# MAPE-CUN-Large-032.net
KiCad netlist of a schematic drawn in EAGLE
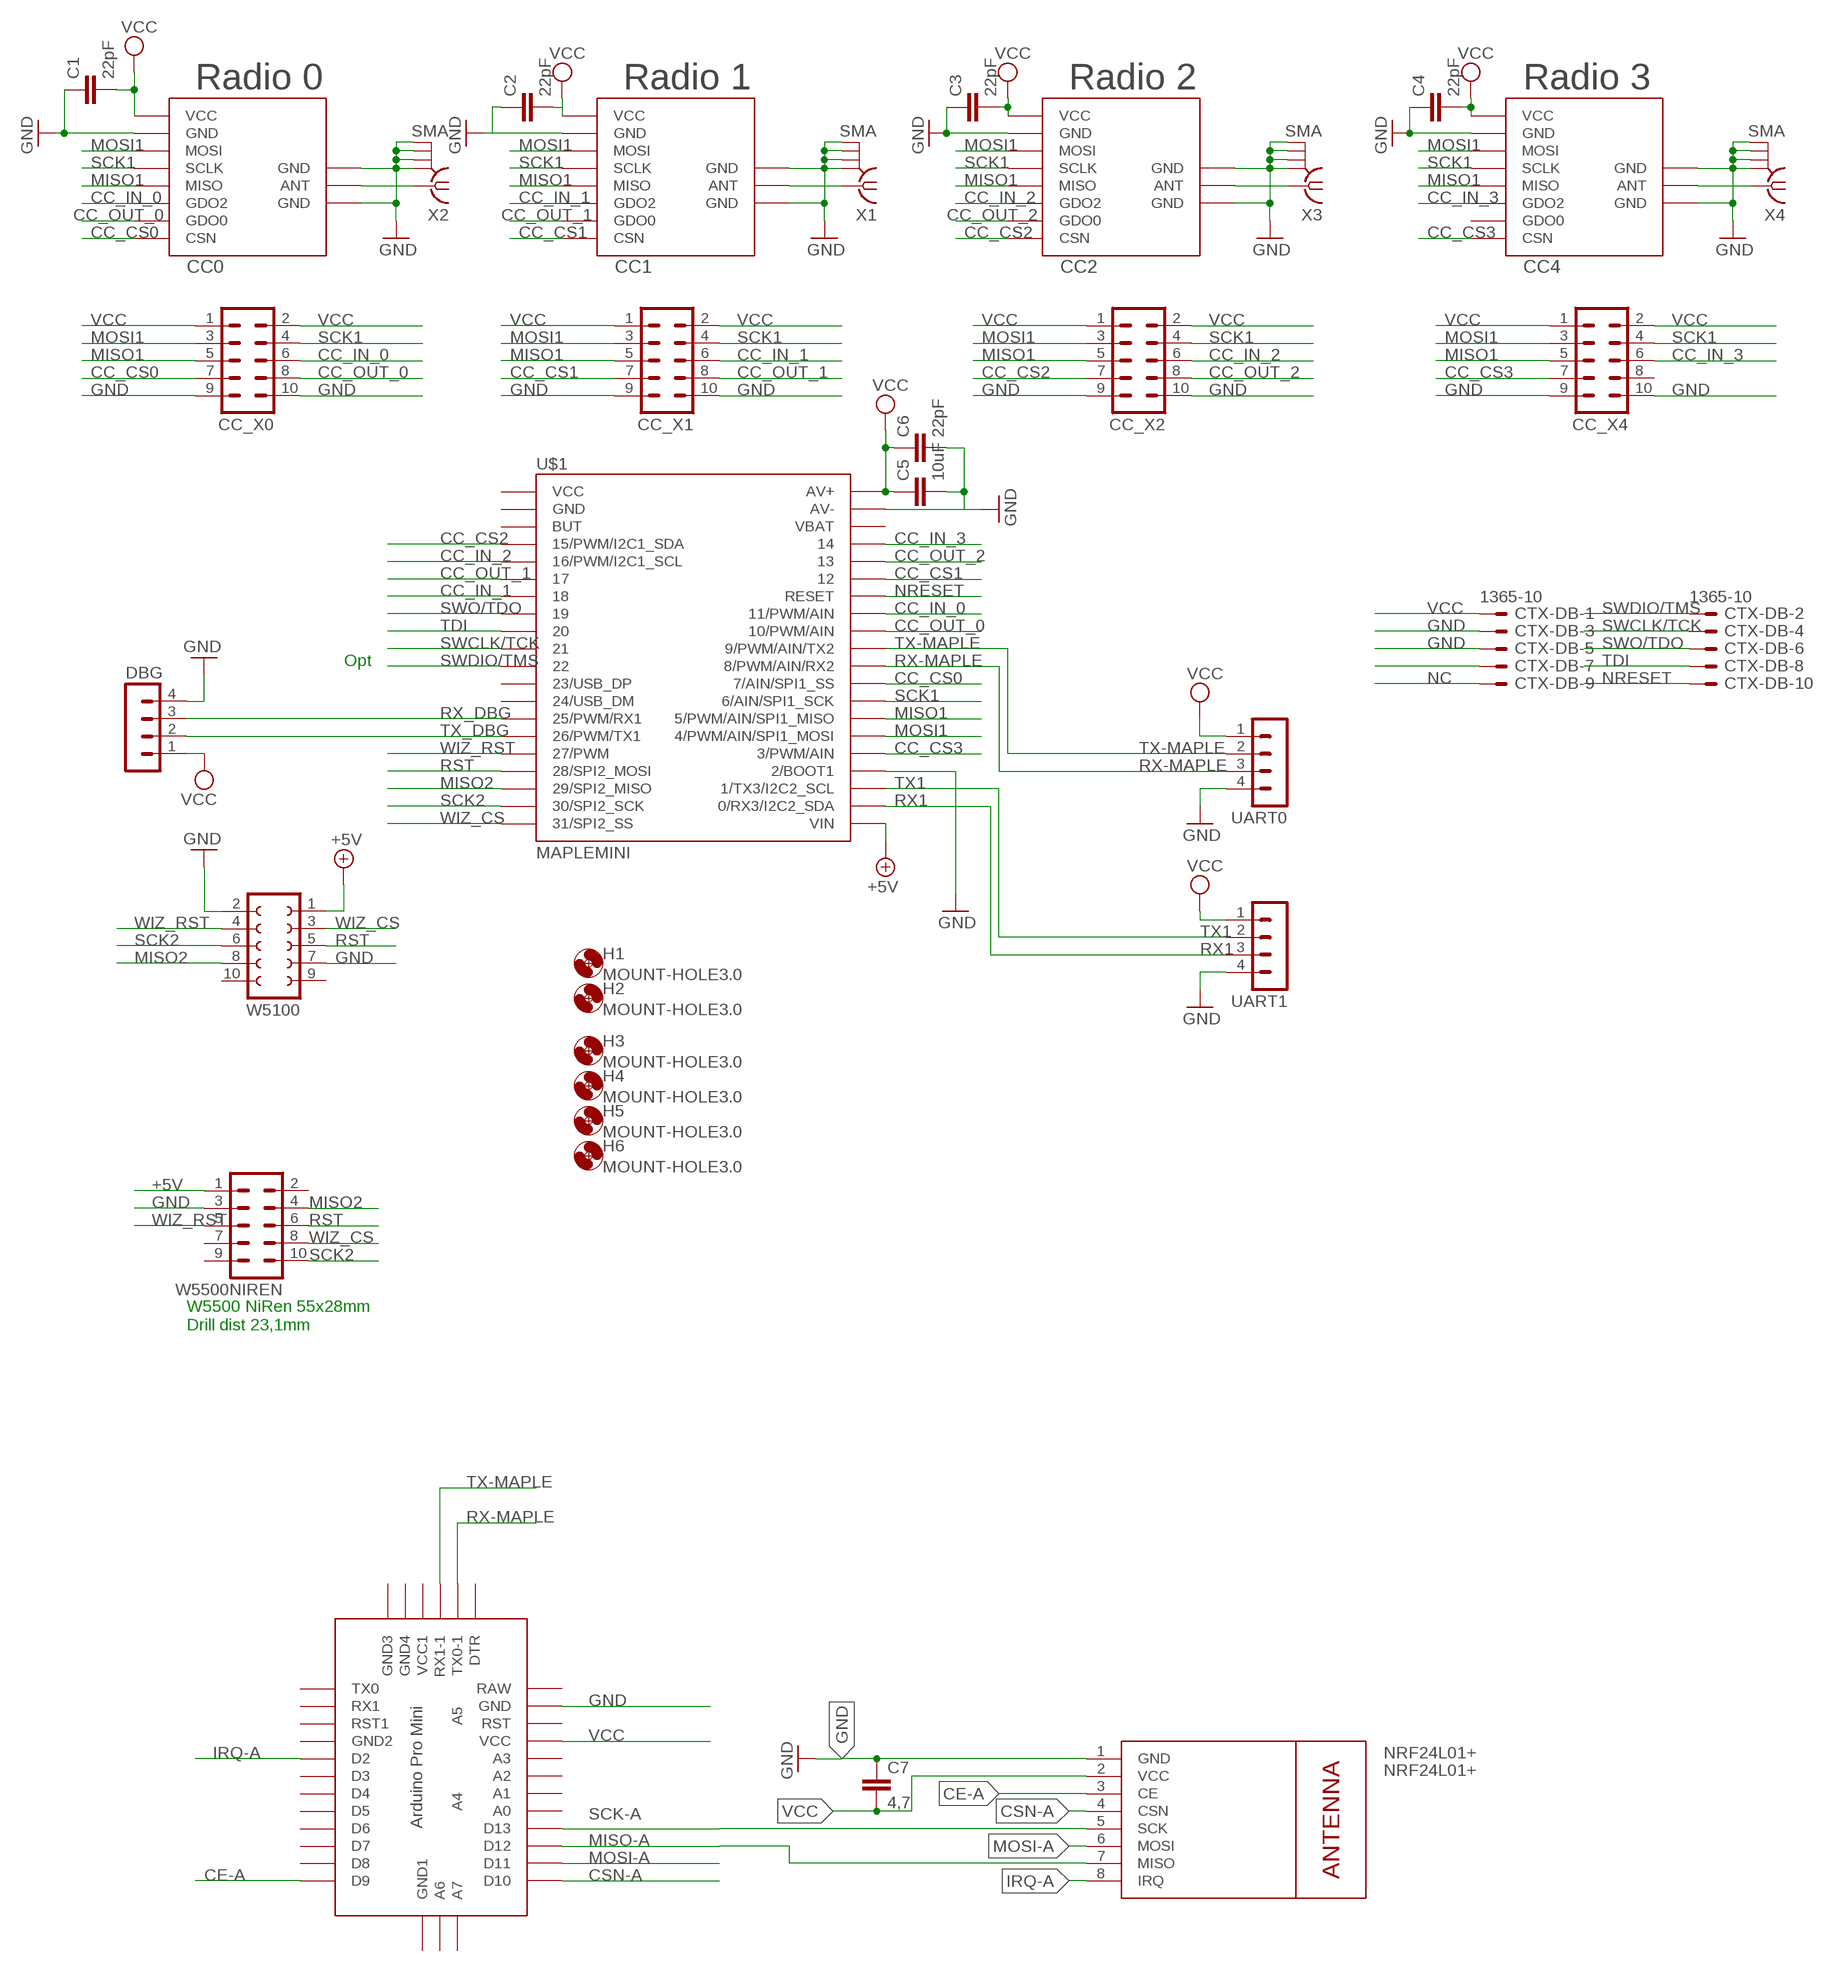
[diagram p0: schematic, sheet 1]

(export (version "E")
  (design (tool "Eeschema 10.0.6"))
  (components
    (comp (ref "C1")
      (value "22pF")
      (footprint "eagle-import:C0805")
      (libsource (lib "eagle-import") (part "C-EUC0805"))
    )
    (comp (ref "C2")
      (value "22pF")
      (footprint "eagle-import:C0805")
      (libsource (lib "eagle-import") (part "C-EUC0805"))
    )
    (comp (ref "C3")
      (value "22pF")
      (footprint "eagle-import:C0805")
      (libsource (lib "eagle-import") (part "C-EUC0805"))
    )
    (comp (ref "C4")
      (value "22pF")
      (footprint "eagle-import:C0805")
      (libsource (lib "eagle-import") (part "C-EUC0805"))
    )
    (comp (ref "C5")
      (value "10uF")
      (footprint "eagle-import:C1210")
      (libsource (lib "eagle-import") (part "C-EUC1210"))
    )
    (comp (ref "C6")
      (value "22pF")
      (footprint "eagle-import:C0805")
      (libsource (lib "eagle-import") (part "C-EUC0805"))
    )
    (comp (ref "C7")
      (value "4,7")
      (footprint "eagle-import:C1210")
      (libsource (lib "eagle-import") (part "C-EUC1210"))
    )
    (comp (ref "CC0")
      (value "CC1101_MODULE1SMD")
      (footprint "eagle-import:CC1101_MODULE1_SMD")
      (libsource (lib "eagle-import") (part "CC1101_MODULE1SMD"))
    )
    (comp (ref "CC1")
      (value "CC1101_MODULE1SMD")
      (footprint "eagle-import:CC1101_MODULE1_SMD")
      (libsource (lib "eagle-import") (part "CC1101_MODULE1SMD"))
    )
    (comp (ref "CC2")
      (value "CC1101_MODULE1SMD")
      (footprint "eagle-import:CC1101_MODULE1_SMD")
      (libsource (lib "eagle-import") (part "CC1101_MODULE1SMD"))
    )
    (comp (ref "CC4")
      (value "CC1101_MODULE1SMD")
      (footprint "eagle-import:CC1101_MODULE1_SMD")
      (libsource (lib "eagle-import") (part "CC1101_MODULE1SMD"))
    )
    (comp (ref "CC_X0")
      (value "MA05-2")
      (footprint "eagle-import:MA05-2")
      (libsource (lib "eagle-import") (part "MA05-2"))
    )
    (comp (ref "CC_X1")
      (value "MA05-2")
      (footprint "eagle-import:MA05-2")
      (libsource (lib "eagle-import") (part "MA05-2"))
    )
    (comp (ref "CC_X2")
      (value "MA05-2")
      (footprint "eagle-import:MA05-2")
      (libsource (lib "eagle-import") (part "MA05-2"))
    )
    (comp (ref "CC_X4")
      (value "MA05-2")
      (footprint "eagle-import:MA05-2")
      (libsource (lib "eagle-import") (part "MA05-2"))
    )
    (comp (ref "CTX-DB")
      (value "1365-10")
      (footprint "eagle-import:1365-10")
      (libsource (lib "eagle-import") (part "1365-10"))
    )
    (comp (ref "DBG")
      (value "MA04-1")
      (footprint "eagle-import:MA04-1")
      (libsource (lib "eagle-import") (part "MA04-1"))
    )
    (comp (ref "H1")
      (value "MOUNT-HOLE3.0")
      (footprint "eagle-import:3,0")
      (libsource (lib "eagle-import") (part "MOUNT-HOLE3.0"))
    )
    (comp (ref "H2")
      (value "MOUNT-HOLE3.0")
      (footprint "eagle-import:3,0")
      (libsource (lib "eagle-import") (part "MOUNT-HOLE3.0"))
    )
    (comp (ref "H3")
      (value "MOUNT-HOLE3.0")
      (footprint "eagle-import:3,0")
      (libsource (lib "eagle-import") (part "MOUNT-HOLE3.0"))
    )
    (comp (ref "H4")
      (value "MOUNT-HOLE3.0")
      (footprint "eagle-import:3,0")
      (libsource (lib "eagle-import") (part "MOUNT-HOLE3.0"))
    )
    (comp (ref "H5")
      (value "MOUNT-HOLE3.0")
      (footprint "eagle-import:3,0")
      (libsource (lib "eagle-import") (part "MOUNT-HOLE3.0"))
    )
    (comp (ref "H6")
      (value "MOUNT-HOLE3.0")
      (footprint "eagle-import:3,0")
      (libsource (lib "eagle-import") (part "MOUNT-HOLE3.0"))
    )
    (comp (ref "NRF24L01+")
      (value "NRF24L01+")
      (footprint "eagle-import:WIRELESS-NRF24L01")
      (libsource (lib "eagle-import") (part "WIRELESS-NRF24L01"))
    )
    (comp (ref "U$1")
      (value "MAPLEMINI")
      (footprint "eagle-import:20-DIP")
      (libsource (lib "eagle-import") (part "MAPLEMINI"))
    )
    (comp (ref "U$2")
      (value "ABK-PRO-MINI")
      (footprint "eagle-import:ABK-PRO-MINI")
      (libsource (lib "eagle-import") (part "ABK-PRO-MINI"))
    )
    (comp (ref "UART0")
      (value "MA04-1")
      (footprint "eagle-import:MA04-1")
      (libsource (lib "eagle-import") (part "MA04-1"))
    )
    (comp (ref "UART1")
      (value "MA04-1")
      (footprint "eagle-import:MA04-1")
      (libsource (lib "eagle-import") (part "MA04-1"))
    )
    (comp (ref "W5100")
      (value "FE05-2")
      (footprint "eagle-import:FE05-2")
      (libsource (lib "eagle-import") (part "FE05-2"))
    )
    (comp (ref "W5500NIREN")
      (value "MA05-2")
      (footprint "eagle-import:MA05-2")
      (libsource (lib "eagle-import") (part "MA05-2"))
    )
    (comp (ref "X1")
      (value "SMA")
      (footprint "eagle-import:SMA")
      (libsource (lib "eagle-import") (part "SMA"))
    )
    (comp (ref "X2")
      (value "SMA")
      (footprint "eagle-import:SMA")
      (libsource (lib "eagle-import") (part "SMA"))
    )
    (comp (ref "X3")
      (value "SMA")
      (footprint "eagle-import:SMA")
      (libsource (lib "eagle-import") (part "SMA"))
    )
    (comp (ref "X4")
      (value "SMA")
      (footprint "eagle-import:SMA")
      (libsource (lib "eagle-import") (part "SMA"))
    )
  )
  (nets
    (net (code "1") (name "+5V") (class "Default")
      (node (ref "U$1") (pin "21") (pinfunction "VIN_21") (pintype "bidirectional"))
      (node (ref "W5100") (pin "1") (pinfunction "1_1") (pintype "passive"))
      (node (ref "W5500NIREN") (pin "1") (pinfunction "1_1") (pintype "passive"))
    )
    (net (code "2") (name "/CC_CS0") (class "Default")
      (node (ref "CC0") (pin "CSN") (pinfunction "CSN_CSN") (pintype "bidirectional"))
      (node (ref "CC_X0") (pin "7") (pinfunction "7_7") (pintype "passive"))
      (node (ref "U$1") (pin "29") (pinfunction "7/AIN/SPI1_SS_29") (pintype "bidirectional"))
    )
    (net (code "3") (name "/CC_CS1") (class "Default")
      (node (ref "CC1") (pin "CSN") (pinfunction "CSN_CSN") (pintype "bidirectional"))
      (node (ref "CC_X1") (pin "7") (pinfunction "7_7") (pintype "passive"))
      (node (ref "U$1") (pin "35") (pinfunction "12_35") (pintype "bidirectional"))
    )
    (net (code "4") (name "/CC_CS2") (class "Default")
      (node (ref "CC2") (pin "CSN") (pinfunction "CSN_CSN") (pintype "bidirectional"))
      (node (ref "CC_X2") (pin "7") (pinfunction "7_7") (pintype "passive"))
      (node (ref "U$1") (pin "4") (pinfunction "15/PWM/I2C1_SDA_4") (pintype "bidirectional"))
    )
    (net (code "5") (name "/CC_CS3") (class "Default")
      (node (ref "CC4") (pin "CSN") (pinfunction "CSN_CSN") (pintype "bidirectional"))
      (node (ref "CC_X4") (pin "7") (pinfunction "7_7") (pintype "passive"))
      (node (ref "U$1") (pin "25") (pinfunction "3/PWM/AIN_25") (pintype "bidirectional"))
    )
    (net (code "6") (name "/CC_IN_0") (class "Default")
      (node (ref "CC0") (pin "GDO2") (pinfunction "GDO2_GDO2") (pintype "bidirectional"))
      (node (ref "CC_X0") (pin "6") (pinfunction "6_6") (pintype "passive"))
      (node (ref "U$1") (pin "33") (pinfunction "11/PWM/AIN_33") (pintype "bidirectional"))
    )
    (net (code "7") (name "/CC_IN_1") (class "Default")
      (node (ref "CC1") (pin "GDO2") (pinfunction "GDO2_GDO2") (pintype "bidirectional"))
      (node (ref "CC_X1") (pin "6") (pinfunction "6_6") (pintype "passive"))
      (node (ref "U$1") (pin "7") (pinfunction "18_7") (pintype "bidirectional"))
    )
    (net (code "8") (name "/CC_IN_2") (class "Default")
      (node (ref "CC2") (pin "GDO2") (pinfunction "GDO2_GDO2") (pintype "bidirectional"))
      (node (ref "CC_X2") (pin "6") (pinfunction "6_6") (pintype "passive"))
      (node (ref "U$1") (pin "5") (pinfunction "16/PWM/I2C1_SCL_5") (pintype "bidirectional"))
    )
    (net (code "9") (name "/CC_IN_3") (class "Default")
      (node (ref "CC4") (pin "GDO2") (pinfunction "GDO2_GDO2") (pintype "bidirectional"))
      (node (ref "CC_X4") (pin "6") (pinfunction "6_6") (pintype "passive"))
      (node (ref "U$1") (pin "37") (pinfunction "14_37") (pintype "bidirectional"))
    )
    (net (code "10") (name "/CC_OUT_0") (class "Default")
      (node (ref "CC0") (pin "GDO0") (pinfunction "GDO0_GDO0") (pintype "bidirectional"))
      (node (ref "CC_X0") (pin "8") (pinfunction "8_8") (pintype "passive"))
      (node (ref "U$1") (pin "32") (pinfunction "10/PWM/AIN_32") (pintype "bidirectional"))
    )
    (net (code "11") (name "/CC_OUT_1") (class "Default")
      (node (ref "CC1") (pin "GDO0") (pinfunction "GDO0_GDO0") (pintype "bidirectional"))
      (node (ref "CC_X1") (pin "8") (pinfunction "8_8") (pintype "passive"))
      (node (ref "U$1") (pin "6") (pinfunction "17_6") (pintype "bidirectional"))
    )
    (net (code "12") (name "/CC_OUT_2") (class "Default")
      (node (ref "CC2") (pin "GDO0") (pinfunction "GDO0_GDO0") (pintype "bidirectional"))
      (node (ref "CC_X2") (pin "8") (pinfunction "8_8") (pintype "passive"))
      (node (ref "U$1") (pin "36") (pinfunction "13_36") (pintype "bidirectional"))
    )
    (net (code "13") (name "/MISO-A") (class "Default")
      (node (ref "NRF24L01+") (pin "7") (pinfunction "MISO_7") (pintype "bidirectional"))
      (node (ref "U$2") (pin "D12") (pinfunction "D12_D12") (pintype "bidirectional"))
    )
    (net (code "14") (name "/MISO1") (class "Default")
      (node (ref "CC0") (pin "MISO") (pinfunction "MISO_MISO") (pintype "bidirectional"))
      (node (ref "CC1") (pin "MISO") (pinfunction "MISO_MISO") (pintype "bidirectional"))
      (node (ref "CC2") (pin "MISO") (pinfunction "MISO_MISO") (pintype "bidirectional"))
      (node (ref "CC4") (pin "MISO") (pinfunction "MISO_MISO") (pintype "bidirectional"))
      (node (ref "CC_X0") (pin "5") (pinfunction "5_5") (pintype "passive"))
      (node (ref "CC_X1") (pin "5") (pinfunction "5_5") (pintype "passive"))
      (node (ref "CC_X2") (pin "5") (pinfunction "5_5") (pintype "passive"))
      (node (ref "CC_X4") (pin "5") (pinfunction "5_5") (pintype "passive"))
      (node (ref "U$1") (pin "27") (pinfunction "5/PWM/AIN/SPI1_MISO_27") (pintype "bidirectional"))
    )
    (net (code "15") (name "/MISO2") (class "Default")
      (node (ref "U$1") (pin "18") (pinfunction "29/SPI2_MISO_18") (pintype "bidirectional"))
      (node (ref "W5100") (pin "8") (pinfunction "8_8") (pintype "passive"))
      (node (ref "W5500NIREN") (pin "4") (pinfunction "4_4") (pintype "passive"))
    )
    (net (code "16") (name "/MOSI1") (class "Default")
      (node (ref "CC0") (pin "MOSI") (pinfunction "MOSI_MOSI") (pintype "bidirectional"))
      (node (ref "CC1") (pin "MOSI") (pinfunction "MOSI_MOSI") (pintype "bidirectional"))
      (node (ref "CC2") (pin "MOSI") (pinfunction "MOSI_MOSI") (pintype "bidirectional"))
      (node (ref "CC4") (pin "MOSI") (pinfunction "MOSI_MOSI") (pintype "bidirectional"))
      (node (ref "CC_X0") (pin "3") (pinfunction "3_3") (pintype "passive"))
      (node (ref "CC_X1") (pin "3") (pinfunction "3_3") (pintype "passive"))
      (node (ref "CC_X2") (pin "3") (pinfunction "3_3") (pintype "passive"))
      (node (ref "CC_X4") (pin "3") (pinfunction "3_3") (pintype "passive"))
      (node (ref "U$1") (pin "26") (pinfunction "4/PWM/AIN/SPI1_MOSI_26") (pintype "bidirectional"))
    )
    (net (code "17") (name "/NC") (class "Default")
      (node (ref "CTX-DB") (pin "9") (pinfunction "S_9") (pintype "passive"))
    )
    (net (code "18") (name "/NRESET") (class "Default")
      (node (ref "CTX-DB") (pin "10") (pinfunction "S_10") (pintype "passive"))
      (node (ref "U$1") (pin "34") (pinfunction "RESET_34") (pintype "bidirectional"))
    )
    (net (code "19") (name "/RST") (class "Default")
      (node (ref "U$1") (pin "17") (pinfunction "28/SPI2_MOSI_17") (pintype "bidirectional"))
      (node (ref "W5100") (pin "5") (pinfunction "5_5") (pintype "passive"))
      (node (ref "W5500NIREN") (pin "6") (pinfunction "6_6") (pintype "passive"))
    )
    (net (code "20") (name "/RX-MAPLE") (class "Default")
      (node (ref "U$1") (pin "30") (pinfunction "8/PWM/AIN/RX2_30") (pintype "bidirectional"))
      (node (ref "U$2") (pin "TX0-1") (pinfunction "TX0-1_TX0-1") (pintype "bidirectional"))
      (node (ref "UART0") (pin "3") (pinfunction "3_3") (pintype "passive"))
    )
    (net (code "21") (name "/RX1") (class "Default")
      (node (ref "U$1") (pin "22") (pinfunction "0/RX3/I2C2_SDA_22") (pintype "bidirectional"))
      (node (ref "UART1") (pin "3") (pinfunction "3_3") (pintype "passive"))
    )
    (net (code "22") (name "/RX_DBG") (class "Default")
      (node (ref "DBG") (pin "3") (pinfunction "3_3") (pintype "passive"))
      (node (ref "U$1") (pin "14") (pinfunction "25/PWM/RX1_14") (pintype "bidirectional"))
    )
    (net (code "23") (name "/SCK-A") (class "Default")
      (node (ref "NRF24L01+") (pin "5") (pinfunction "SCK_5") (pintype "bidirectional"))
      (node (ref "U$2") (pin "D13") (pinfunction "D13_D13") (pintype "bidirectional"))
    )
    (net (code "24") (name "/SCK1") (class "Default")
      (node (ref "CC0") (pin "SCLK") (pinfunction "SCLK_SCLK") (pintype "bidirectional"))
      (node (ref "CC1") (pin "SCLK") (pinfunction "SCLK_SCLK") (pintype "bidirectional"))
      (node (ref "CC2") (pin "SCLK") (pinfunction "SCLK_SCLK") (pintype "bidirectional"))
      (node (ref "CC4") (pin "SCLK") (pinfunction "SCLK_SCLK") (pintype "bidirectional"))
      (node (ref "CC_X0") (pin "4") (pinfunction "4_4") (pintype "passive"))
      (node (ref "CC_X1") (pin "4") (pinfunction "4_4") (pintype "passive"))
      (node (ref "CC_X2") (pin "4") (pinfunction "4_4") (pintype "passive"))
      (node (ref "CC_X4") (pin "4") (pinfunction "4_4") (pintype "passive"))
      (node (ref "U$1") (pin "28") (pinfunction "6/AIN/SPI1_SCK_28") (pintype "bidirectional"))
    )
    (net (code "25") (name "/SCK2") (class "Default")
      (node (ref "U$1") (pin "19") (pinfunction "30/SPI2_SCK_19") (pintype "bidirectional"))
      (node (ref "W5100") (pin "6") (pinfunction "6_6") (pintype "passive"))
      (node (ref "W5500NIREN") (pin "10") (pinfunction "10_10") (pintype "passive"))
    )
    (net (code "26") (name "/SWCLK{slash}TCK") (class "Default")
      (node (ref "CTX-DB") (pin "4") (pinfunction "S_4") (pintype "passive"))
      (node (ref "U$1") (pin "10") (pinfunction "21_10") (pintype "bidirectional"))
    )
    (net (code "27") (name "/SWDIO{slash}TMS") (class "Default")
      (node (ref "CTX-DB") (pin "2") (pinfunction "S_2") (pintype "passive"))
      (node (ref "U$1") (pin "11") (pinfunction "22_11") (pintype "bidirectional"))
    )
    (net (code "28") (name "/SWO{slash}TDO") (class "Default")
      (node (ref "CTX-DB") (pin "6") (pinfunction "S_6") (pintype "passive"))
      (node (ref "U$1") (pin "8") (pinfunction "19_8") (pintype "bidirectional"))
    )
    (net (code "29") (name "/TDI") (class "Default")
      (node (ref "CTX-DB") (pin "8") (pinfunction "S_8") (pintype "passive"))
      (node (ref "U$1") (pin "9") (pinfunction "20_9") (pintype "bidirectional"))
    )
    (net (code "30") (name "/TX-MAPLE") (class "Default")
      (node (ref "U$1") (pin "31") (pinfunction "9/PWM/AIN/TX2_31") (pintype "bidirectional"))
      (node (ref "U$2") (pin "RX1-1") (pinfunction "RX1-1_RX1-1") (pintype "bidirectional"))
      (node (ref "UART0") (pin "2") (pinfunction "2_2") (pintype "passive"))
    )
    (net (code "31") (name "/TX1") (class "Default")
      (node (ref "U$1") (pin "23") (pinfunction "1/TX3/I2C2_SCL_23") (pintype "bidirectional"))
      (node (ref "UART1") (pin "2") (pinfunction "2_2") (pintype "passive"))
    )
    (net (code "32") (name "/TX_DBG") (class "Default")
      (node (ref "DBG") (pin "2") (pinfunction "2_2") (pintype "passive"))
      (node (ref "U$1") (pin "15") (pinfunction "26/PWM/TX1_15") (pintype "bidirectional"))
    )
    (net (code "33") (name "/WIZ_CS") (class "Default")
      (node (ref "U$1") (pin "20") (pinfunction "31/SPI2_SS_20") (pintype "bidirectional"))
      (node (ref "W5100") (pin "3") (pinfunction "3_3") (pintype "passive"))
      (node (ref "W5500NIREN") (pin "8") (pinfunction "8_8") (pintype "passive"))
    )
    (net (code "34") (name "/WIZ_RST") (class "Default")
      (node (ref "U$1") (pin "16") (pinfunction "27/PWM_16") (pintype "bidirectional"))
      (node (ref "W5100") (pin "4") (pinfunction "4_4") (pintype "passive"))
      (node (ref "W5500NIREN") (pin "5") (pinfunction "5_5") (pintype "passive"))
    )
    (net (code "35") (name "CE-A") (class "Default")
      (node (ref "NRF24L01+") (pin "3") (pinfunction "CE_3") (pintype "bidirectional"))
      (node (ref "U$2") (pin "D9") (pinfunction "D9_D9") (pintype "bidirectional"))
    )
    (net (code "36") (name "CSN-A") (class "Default")
      (node (ref "NRF24L01+") (pin "4") (pinfunction "CSN_4") (pintype "bidirectional"))
      (node (ref "U$2") (pin "D10") (pinfunction "D10_D10") (pintype "bidirectional"))
    )
    (net (code "37") (name "GND") (class "Default")
      (node (ref "C1") (pin "1") (pinfunction "1_1") (pintype "passive"))
      (node (ref "C2") (pin "1") (pinfunction "1_1") (pintype "passive"))
      (node (ref "C3") (pin "1") (pinfunction "1_1") (pintype "passive"))
      (node (ref "C4") (pin "1") (pinfunction "1_1") (pintype "passive"))
      (node (ref "C5") (pin "2") (pinfunction "2_2") (pintype "passive"))
      (node (ref "C6") (pin "2") (pinfunction "2_2") (pintype "passive"))
      (node (ref "C7") (pin "1") (pinfunction "1_1") (pintype "passive"))
      (node (ref "CC0") (pin "GND@0") (pinfunction "GND_GND@0") (pintype "power_in"))
      (node (ref "CC0") (pin "GND@1") (pinfunction "GND_GND@1") (pintype "power_in"))
      (node (ref "CC0") (pin "GND@2") (pinfunction "GND_GND@2") (pintype "power_in"))
      (node (ref "CC1") (pin "GND@0") (pinfunction "GND_GND@0") (pintype "power_in"))
      (node (ref "CC1") (pin "GND@1") (pinfunction "GND_GND@1") (pintype "power_in"))
      (node (ref "CC1") (pin "GND@2") (pinfunction "GND_GND@2") (pintype "power_in"))
      (node (ref "CC2") (pin "GND@0") (pinfunction "GND_GND@0") (pintype "power_in"))
      (node (ref "CC2") (pin "GND@1") (pinfunction "GND_GND@1") (pintype "power_in"))
      (node (ref "CC2") (pin "GND@2") (pinfunction "GND_GND@2") (pintype "power_in"))
      (node (ref "CC4") (pin "GND@0") (pinfunction "GND_GND@0") (pintype "power_in"))
      (node (ref "CC4") (pin "GND@1") (pinfunction "GND_GND@1") (pintype "power_in"))
      (node (ref "CC4") (pin "GND@2") (pinfunction "GND_GND@2") (pintype "power_in"))
      (node (ref "CC_X0") (pin "10") (pinfunction "10_10") (pintype "passive"))
      (node (ref "CC_X0") (pin "9") (pinfunction "9_9") (pintype "passive"))
      (node (ref "CC_X1") (pin "10") (pinfunction "10_10") (pintype "passive"))
      (node (ref "CC_X1") (pin "9") (pinfunction "9_9") (pintype "passive"))
      (node (ref "CC_X2") (pin "10") (pinfunction "10_10") (pintype "passive"))
      (node (ref "CC_X2") (pin "9") (pinfunction "9_9") (pintype "passive"))
      (node (ref "CC_X4") (pin "10") (pinfunction "10_10") (pintype "passive"))
      (node (ref "CC_X4") (pin "9") (pinfunction "9_9") (pintype "passive"))
      (node (ref "CTX-DB") (pin "3") (pinfunction "S_3") (pintype "passive"))
      (node (ref "CTX-DB") (pin "5") (pinfunction "S_5") (pintype "passive"))
      (node (ref "DBG") (pin "4") (pinfunction "4_4") (pintype "passive"))
      (node (ref "NRF24L01+") (pin "1") (pinfunction "GND_1") (pintype "power_in"))
      (node (ref "U$1") (pin "24") (pinfunction "2/BOOT1_24") (pintype "bidirectional"))
      (node (ref "U$1") (pin "39") (pinfunction "AV-_39") (pintype "bidirectional"))
      (node (ref "U$2") (pin "GND") (pinfunction "GND_GND") (pintype "bidirectional"))
      (node (ref "UART0") (pin "4") (pinfunction "4_4") (pintype "passive"))
      (node (ref "UART1") (pin "4") (pinfunction "4_4") (pintype "passive"))
      (node (ref "W5100") (pin "2") (pinfunction "2_2") (pintype "passive"))
      (node (ref "W5100") (pin "7") (pinfunction "7_7") (pintype "passive"))
      (node (ref "W5500NIREN") (pin "3") (pinfunction "3_3") (pintype "passive"))
      (node (ref "X1") (pin "GND@1") (pinfunction "2_GND@1") (pintype "passive"))
      (node (ref "X1") (pin "GND@2") (pinfunction "3_GND@2") (pintype "passive"))
      (node (ref "X1") (pin "GND@3") (pinfunction "4_GND@3") (pintype "passive"))
      (node (ref "X1") (pin "GND@4") (pinfunction "5_GND@4") (pintype "passive"))
      (node (ref "X2") (pin "GND@1") (pinfunction "2_GND@1") (pintype "passive"))
      (node (ref "X2") (pin "GND@2") (pinfunction "3_GND@2") (pintype "passive"))
      (node (ref "X2") (pin "GND@3") (pinfunction "4_GND@3") (pintype "passive"))
      (node (ref "X2") (pin "GND@4") (pinfunction "5_GND@4") (pintype "passive"))
      (node (ref "X3") (pin "GND@1") (pinfunction "2_GND@1") (pintype "passive"))
      (node (ref "X3") (pin "GND@2") (pinfunction "3_GND@2") (pintype "passive"))
      (node (ref "X3") (pin "GND@3") (pinfunction "4_GND@3") (pintype "passive"))
      (node (ref "X3") (pin "GND@4") (pinfunction "5_GND@4") (pintype "passive"))
      (node (ref "X4") (pin "GND@1") (pinfunction "2_GND@1") (pintype "passive"))
      (node (ref "X4") (pin "GND@2") (pinfunction "3_GND@2") (pintype "passive"))
      (node (ref "X4") (pin "GND@3") (pinfunction "4_GND@3") (pintype "passive"))
      (node (ref "X4") (pin "GND@4") (pinfunction "5_GND@4") (pintype "passive"))
    )
    (net (code "38") (name "IRQ-A") (class "Default")
      (node (ref "NRF24L01+") (pin "8") (pinfunction "IRQ_8") (pintype "bidirectional"))
      (node (ref "U$2") (pin "D2") (pinfunction "D2_D2") (pintype "bidirectional"))
    )
    (net (code "39") (name "MOSI-A") (class "Default")
      (node (ref "NRF24L01+") (pin "6") (pinfunction "MOSI_6") (pintype "bidirectional"))
      (node (ref "U$2") (pin "D11") (pinfunction "D11_D11") (pintype "bidirectional"))
    )
    (net (code "40") (name "Net-(CC0-PadANT)") (class "Default")
      (node (ref "CC0") (pin "ANT") (pinfunction "ANT_ANT") (pintype "output"))
      (node (ref "X2") (pin "1") (pinfunction "1_1") (pintype "passive"))
    )
    (net (code "41") (name "Net-(CC1-PadANT)") (class "Default")
      (node (ref "CC1") (pin "ANT") (pinfunction "ANT_ANT") (pintype "output"))
      (node (ref "X1") (pin "1") (pinfunction "1_1") (pintype "passive"))
    )
    (net (code "42") (name "Net-(CC2-PadANT)") (class "Default")
      (node (ref "CC2") (pin "ANT") (pinfunction "ANT_ANT") (pintype "output"))
      (node (ref "X3") (pin "1") (pinfunction "1_1") (pintype "passive"))
    )
    (net (code "43") (name "Net-(CC4-PadANT)") (class "Default")
      (node (ref "CC4") (pin "ANT") (pinfunction "ANT_ANT") (pintype "output"))
      (node (ref "X4") (pin "1") (pinfunction "1_1") (pintype "passive"))
    )
    (net (code "44") (name "VCC") (class "Default")
      (node (ref "C1") (pin "2") (pinfunction "2_2") (pintype "passive"))
      (node (ref "C2") (pin "2") (pinfunction "2_2") (pintype "passive"))
      (node (ref "C3") (pin "2") (pinfunction "2_2") (pintype "passive"))
      (node (ref "C4") (pin "2") (pinfunction "2_2") (pintype "passive"))
      (node (ref "C5") (pin "1") (pinfunction "1_1") (pintype "passive"))
      (node (ref "C6") (pin "1") (pinfunction "1_1") (pintype "passive"))
      (node (ref "C7") (pin "2") (pinfunction "2_2") (pintype "passive"))
      (node (ref "CC0") (pin "VCC") (pinfunction "VCC_VCC") (pintype "power_in"))
      (node (ref "CC1") (pin "VCC") (pinfunction "VCC_VCC") (pintype "power_in"))
      (node (ref "CC2") (pin "VCC") (pinfunction "VCC_VCC") (pintype "power_in"))
      (node (ref "CC4") (pin "VCC") (pinfunction "VCC_VCC") (pintype "power_in"))
      (node (ref "CC_X0") (pin "1") (pinfunction "1_1") (pintype "passive"))
      (node (ref "CC_X0") (pin "2") (pinfunction "2_2") (pintype "passive"))
      (node (ref "CC_X1") (pin "1") (pinfunction "1_1") (pintype "passive"))
      (node (ref "CC_X1") (pin "2") (pinfunction "2_2") (pintype "passive"))
      (node (ref "CC_X2") (pin "1") (pinfunction "1_1") (pintype "passive"))
      (node (ref "CC_X2") (pin "2") (pinfunction "2_2") (pintype "passive"))
      (node (ref "CC_X4") (pin "1") (pinfunction "1_1") (pintype "passive"))
      (node (ref "CC_X4") (pin "2") (pinfunction "2_2") (pintype "passive"))
      (node (ref "CTX-DB") (pin "1") (pinfunction "S_1") (pintype "passive"))
      (node (ref "DBG") (pin "1") (pinfunction "1_1") (pintype "passive"))
      (node (ref "NRF24L01+") (pin "2") (pinfunction "VCC_2") (pintype "power_in"))
      (node (ref "U$1") (pin "40") (pinfunction "AV+_40") (pintype "bidirectional"))
      (node (ref "U$2") (pin "VCC") (pinfunction "VCC_VCC") (pintype "bidirectional"))
      (node (ref "UART0") (pin "1") (pinfunction "1_1") (pintype "passive"))
      (node (ref "UART1") (pin "1") (pinfunction "1_1") (pintype "passive"))
    )
    (net (code "45") (name "unconnected-(CC4-PadGDO0)") (class "Default")
      (node (ref "CC4") (pin "GDO0") (pinfunction "GDO0_GDO0") (pintype "bidirectional"))
    )
    (net (code "46") (name "unconnected-(CC_X4-Pad8)") (class "Default")
      (node (ref "CC_X4") (pin "8") (pinfunction "8_8") (pintype "passive"))
    )
    (net (code "47") (name "unconnected-(CTX-DBH-S-Pad7)") (class "Default")
      (node (ref "CTX-DB") (pin "7") (pinfunction "S_7") (pintype "passive"))
    )
    (net (code "48") (name "unconnected-(U$1-23{slash}USB_DP-Pad12)") (class "Default")
      (node (ref "U$1") (pin "12") (pinfunction "23/USB_DP_12") (pintype "bidirectional"))
    )
    (net (code "49") (name "unconnected-(U$1-24{slash}USB_DM-Pad13)") (class "Default")
      (node (ref "U$1") (pin "13") (pinfunction "24/USB_DM_13") (pintype "bidirectional"))
    )
    (net (code "50") (name "unconnected-(U$1-BUT-Pad3)") (class "Default")
      (node (ref "U$1") (pin "3") (pinfunction "BUT_3") (pintype "bidirectional"))
    )
    (net (code "51") (name "unconnected-(U$1-GND-Pad2)") (class "Default")
      (node (ref "U$1") (pin "2") (pinfunction "GND_2") (pintype "bidirectional"))
    )
    (net (code "52") (name "unconnected-(U$1-VBAT-Pad38)") (class "Default")
      (node (ref "U$1") (pin "38") (pinfunction "VBAT_38") (pintype "bidirectional"))
    )
    (net (code "53") (name "unconnected-(U$1-VCC-Pad1)") (class "Default")
      (node (ref "U$1") (pin "1") (pinfunction "VCC_1") (pintype "bidirectional"))
    )
    (net (code "54") (name "unconnected-(U$2-GND1-PadGND4)") (class "Default")
      (node (ref "U$2") (pin "GND4") (pinfunction "GND1_GND4") (pintype "bidirectional"))
    )
    (net (code "55") (name "unconnected-(U$2-GND2-PadGND1)") (class "Default")
      (node (ref "U$2") (pin "GND1") (pinfunction "GND2_GND1") (pintype "bidirectional"))
    )
    (net (code "56") (name "unconnected-(U$2-GND3-PadGND2)") (class "Default")
      (node (ref "U$2") (pin "GND2") (pinfunction "GND3_GND2") (pintype "bidirectional"))
    )
    (net (code "57") (name "unconnected-(U$2-GND4-PadGND3)") (class "Default")
      (node (ref "U$2") (pin "GND3") (pinfunction "GND4_GND3") (pintype "bidirectional"))
    )
    (net (code "58") (name "unconnected-(U$2-PadA0)") (class "Default")
      (node (ref "U$2") (pin "A0") (pinfunction "A0_A0") (pintype "bidirectional"))
    )
    (net (code "59") (name "unconnected-(U$2-PadA1)") (class "Default")
      (node (ref "U$2") (pin "A1") (pinfunction "A1_A1") (pintype "bidirectional"))
    )
    (net (code "60") (name "unconnected-(U$2-PadA2)") (class "Default")
      (node (ref "U$2") (pin "A2") (pinfunction "A2_A2") (pintype "bidirectional"))
    )
    (net (code "61") (name "unconnected-(U$2-PadA3)") (class "Default")
      (node (ref "U$2") (pin "A3") (pinfunction "A3_A3") (pintype "bidirectional"))
    )
    (net (code "62") (name "unconnected-(U$2-PadA4)") (class "Default")
      (node (ref "U$2") (pin "A4") (pinfunction "A4_A4") (pintype "bidirectional"))
    )
    (net (code "63") (name "unconnected-(U$2-PadA5)") (class "Default")
      (node (ref "U$2") (pin "A5") (pinfunction "A5_A5") (pintype "bidirectional"))
    )
    (net (code "64") (name "unconnected-(U$2-PadA6)") (class "Default")
      (node (ref "U$2") (pin "A6") (pinfunction "A6_A6") (pintype "bidirectional"))
    )
    (net (code "65") (name "unconnected-(U$2-PadA7)") (class "Default")
      (node (ref "U$2") (pin "A7") (pinfunction "A7_A7") (pintype "bidirectional"))
    )
    (net (code "66") (name "unconnected-(U$2-PadD3)") (class "Default")
      (node (ref "U$2") (pin "D3") (pinfunction "D3_D3") (pintype "bidirectional"))
    )
    (net (code "67") (name "unconnected-(U$2-PadD4)") (class "Default")
      (node (ref "U$2") (pin "D4") (pinfunction "D4_D4") (pintype "bidirectional"))
    )
    (net (code "68") (name "unconnected-(U$2-PadD5)") (class "Default")
      (node (ref "U$2") (pin "D5") (pinfunction "D5_D5") (pintype "bidirectional"))
    )
    (net (code "69") (name "unconnected-(U$2-PadD6)") (class "Default")
      (node (ref "U$2") (pin "D6") (pinfunction "D6_D6") (pintype "bidirectional"))
    )
    (net (code "70") (name "unconnected-(U$2-PadD7)") (class "Default")
      (node (ref "U$2") (pin "D7") (pinfunction "D7_D7") (pintype "bidirectional"))
    )
    (net (code "71") (name "unconnected-(U$2-PadD8)") (class "Default")
      (node (ref "U$2") (pin "D8") (pinfunction "D8_D8") (pintype "bidirectional"))
    )
    (net (code "72") (name "unconnected-(U$2-PadDTR)") (class "Default")
      (node (ref "U$2") (pin "DTR") (pinfunction "DTR_DTR") (pintype "bidirectional"))
    )
    (net (code "73") (name "unconnected-(U$2-PadRAW)") (class "Default")
      (node (ref "U$2") (pin "RAW") (pinfunction "RAW_RAW") (pintype "bidirectional"))
    )
    (net (code "74") (name "unconnected-(U$2-PadRST)") (class "Default")
      (node (ref "U$2") (pin "RST") (pinfunction "RST_RST") (pintype "bidirectional"))
    )
    (net (code "75") (name "unconnected-(U$2-PadRST1)") (class "Default")
      (node (ref "U$2") (pin "RST1") (pinfunction "RST1_RST1") (pintype "bidirectional"))
    )
    (net (code "76") (name "unconnected-(U$2-PadRX1)") (class "Default")
      (node (ref "U$2") (pin "RX1") (pinfunction "RX1_RX1") (pintype "bidirectional"))
    )
    (net (code "77") (name "unconnected-(U$2-PadTX0)") (class "Default")
      (node (ref "U$2") (pin "TX0") (pinfunction "TX0_TX0") (pintype "bidirectional"))
    )
    (net (code "78") (name "unconnected-(U$2-PadVCC1)") (class "Default")
      (node (ref "U$2") (pin "VCC1") (pinfunction "VCC1_VCC1") (pintype "bidirectional"))
    )
    (net (code "79") (name "unconnected-(W5100-Pad9)") (class "Default")
      (node (ref "W5100") (pin "9") (pinfunction "9_9") (pintype "passive"))
    )
    (net (code "80") (name "unconnected-(W5100-Pad10)") (class "Default")
      (node (ref "W5100") (pin "10") (pinfunction "10_10") (pintype "passive"))
    )
    (net (code "81") (name "unconnected-(W5500NIREN-Pad2)") (class "Default")
      (node (ref "W5500NIREN") (pin "2") (pinfunction "2_2") (pintype "passive"))
    )
    (net (code "82") (name "unconnected-(W5500NIREN-Pad7)") (class "Default")
      (node (ref "W5500NIREN") (pin "7") (pinfunction "7_7") (pintype "passive"))
    )
    (net (code "83") (name "unconnected-(W5500NIREN-Pad9)") (class "Default")
      (node (ref "W5500NIREN") (pin "9") (pinfunction "9_9") (pintype "passive"))
    )
  )
)
